# Lavadora.net
KiCad netlist of a schematic drawn in EAGLE
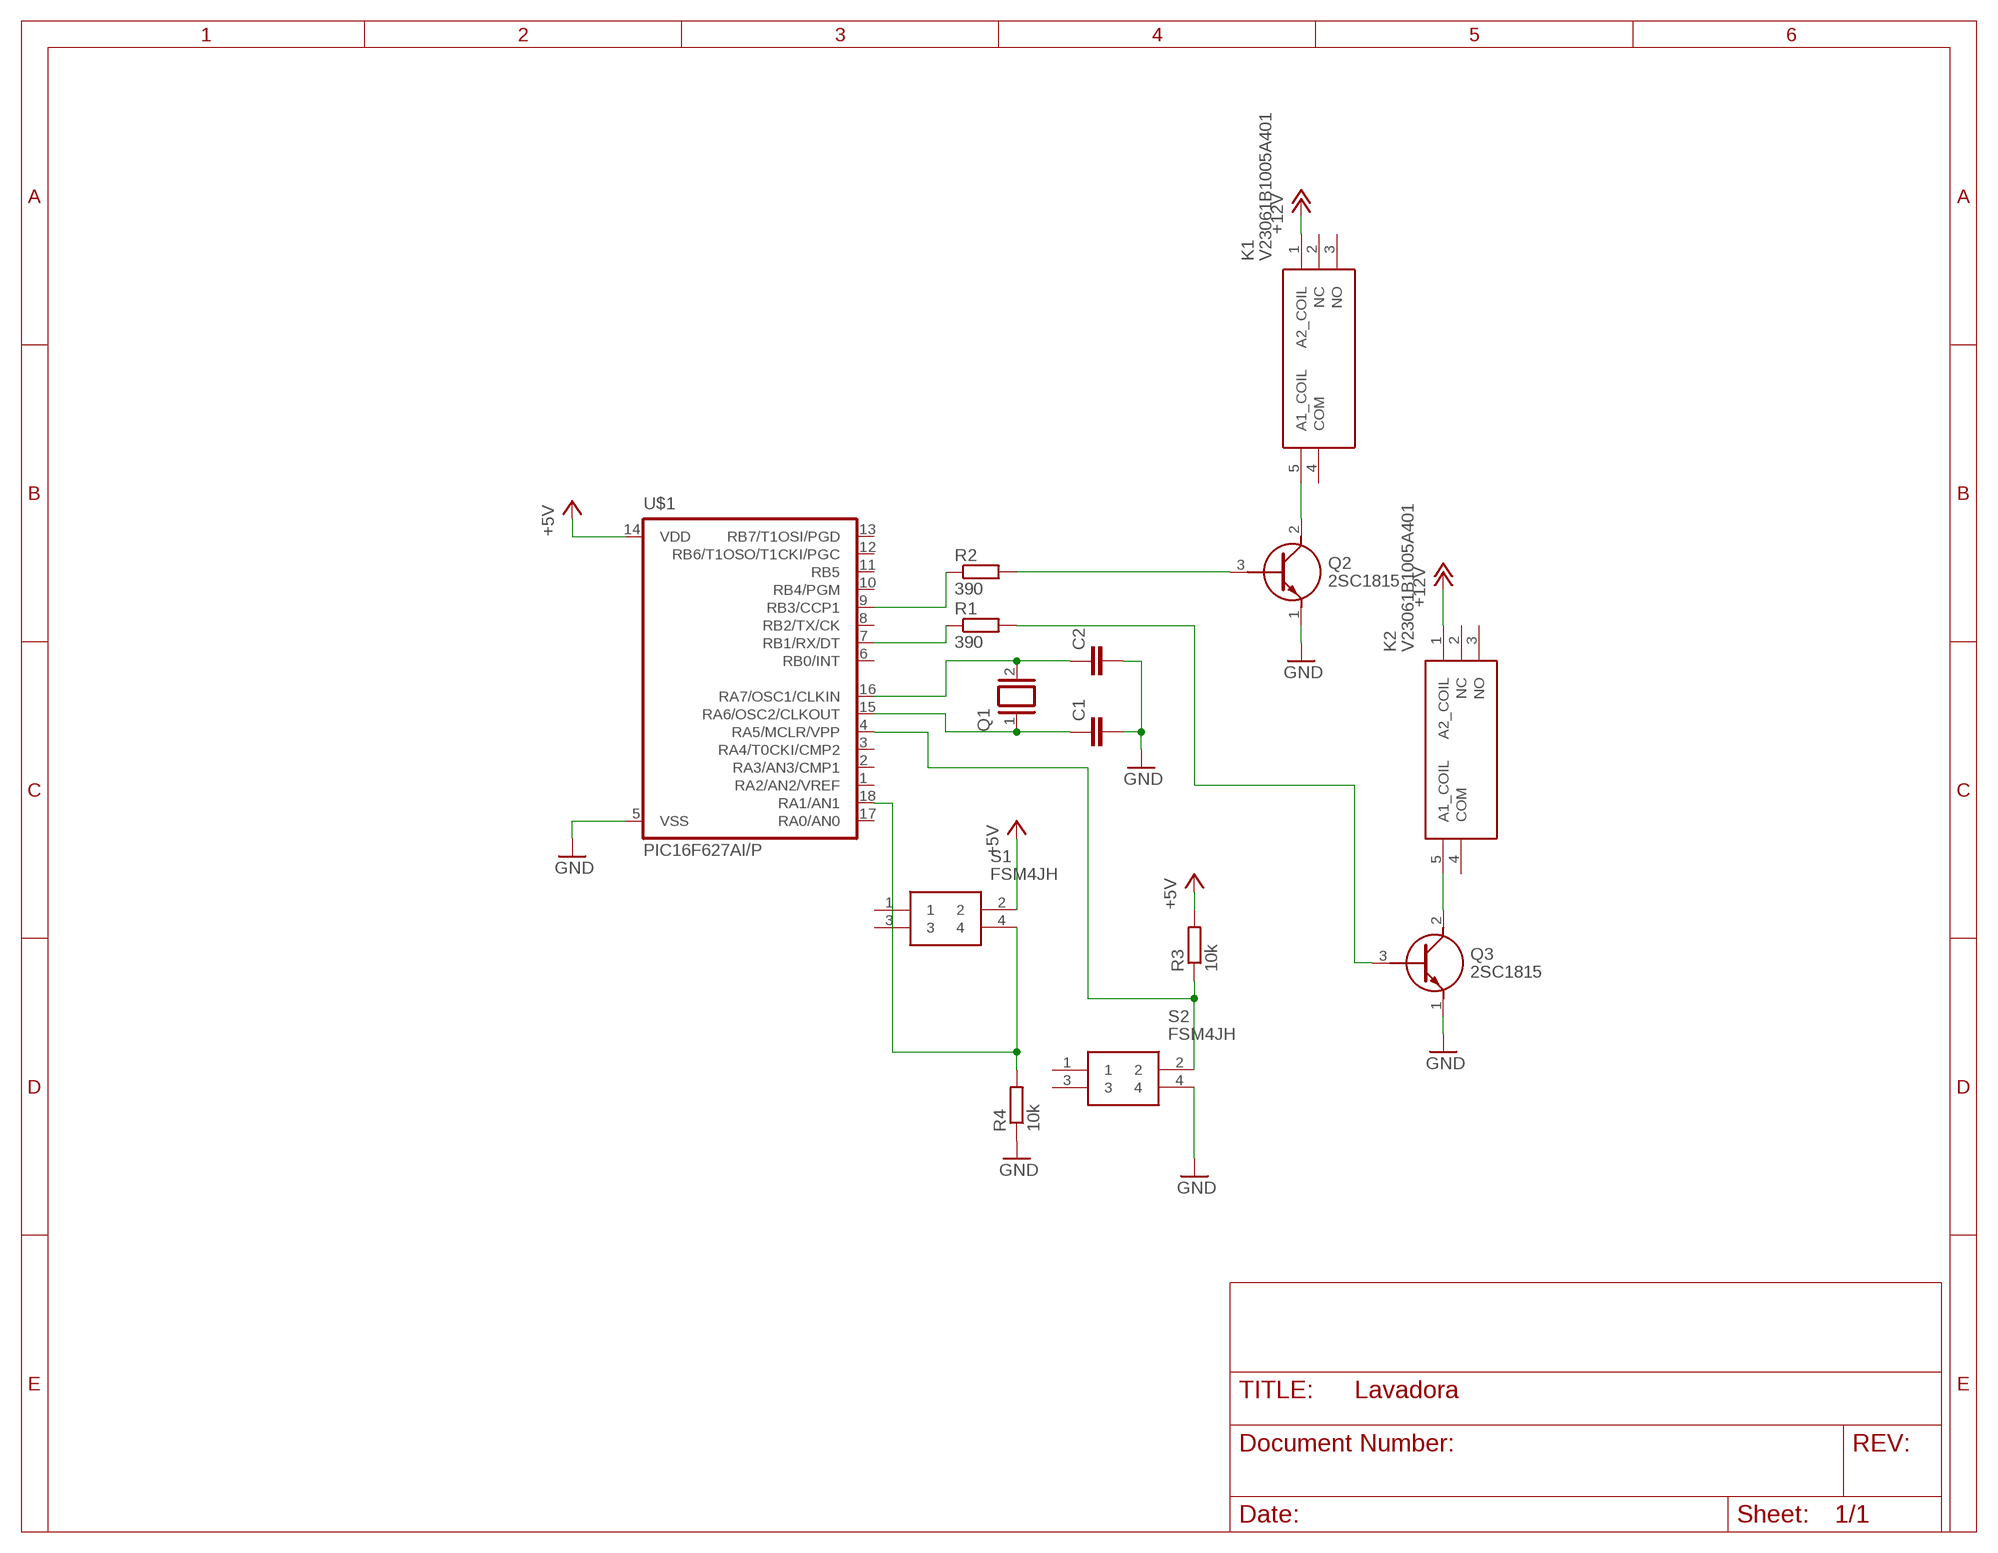
[diagram p0: schematic, sheet 1]

(export (version "E")
  (design (tool "Eeschema 10.0.6"))
  (components
    (comp (ref "C1")
      (value "C-EU025-025X050")
      (footprint "eagle-import:C025-025X050")
      (libsource (lib "eagle-import") (part "C-EU025-025X050"))
    )
    (comp (ref "C2")
      (value "C-EU025-025X050")
      (footprint "eagle-import:C025-025X050")
      (libsource (lib "eagle-import") (part "C-EU025-025X050"))
    )
    (comp (ref "K1")
      (value "V23061B1005A401")
      (footprint "eagle-import:V23061B1005A401")
      (fields (field (name "MOUSER_PART_NUMBER") "655-V23061B1005A401"))
      (libsource (lib "eagle-import") (part "V23061B1005A401"))
    )
    (comp (ref "K2")
      (value "V23061B1005A401")
      (footprint "eagle-import:V23061B1005A401")
      (fields (field (name "MOUSER_PART_NUMBER") "655-V23061B1005A401"))
      (libsource (lib "eagle-import") (part "V23061B1005A401"))
    )
    (comp (ref "Q1")
      (value "XTAL")
      (footprint "eagle-import:Q")
      (libsource (lib "eagle-import") (part "XTAL"))
    )
    (comp (ref "Q2")
      (value "2SC1815")
      (footprint "eagle-import:CS_TO-92")
      (fields (field (name "MOUSER_PART_NUMBER") "610-2SC1815"))
      (libsource (lib "eagle-import") (part "2SC1815"))
    )
    (comp (ref "Q3")
      (value "2SC1815")
      (footprint "eagle-import:CS_TO-92")
      (fields (field (name "MOUSER_PART_NUMBER") "610-2SC1815"))
      (libsource (lib "eagle-import") (part "2SC1815"))
    )
    (comp (ref "R1")
      (value "390")
      (footprint "eagle-import:0207_10")
      (libsource (lib "eagle-import") (part "R-EU_0207/10"))
    )
    (comp (ref "R2")
      (value "390")
      (footprint "eagle-import:0207_10")
      (libsource (lib "eagle-import") (part "R-EU_0207/10"))
    )
    (comp (ref "R3")
      (value "10k")
      (footprint "eagle-import:0207_10")
      (libsource (lib "eagle-import") (part "R-EU_0207/10"))
    )
    (comp (ref "R4")
      (value "10k")
      (footprint "eagle-import:0207_10")
      (libsource (lib "eagle-import") (part "R-EU_0207/10"))
    )
    (comp (ref "S1")
      (value "FSM4JH")
      (footprint "eagle-import:FSM4JH")
      (fields (field (name "MOUSER_PART_NUMBER") "506-FSM4JH"))
      (libsource (lib "eagle-import") (part "FSM4JH"))
    )
    (comp (ref "S2")
      (value "FSM4JH")
      (footprint "eagle-import:FSM4JH")
      (fields (field (name "MOUSER_PART_NUMBER") "506-FSM4JH"))
      (libsource (lib "eagle-import") (part "FSM4JH"))
    )
    (comp (ref "U$1")
      (value "PIC16F627AI/P")
      (footprint "eagle-import:DIL18")
      (libsource (lib "eagle-import") (part "PIC16F627AI/P"))
    )
  )
  (nets
    (net (code "1") (name "+5V") (class "Default")
      (node (ref "R3") (pin "2") (pinfunction "2_2") (pintype "passive"))
      (node (ref "S1") (pin "2") (pinfunction "2_2") (pintype "bidirectional"))
      (node (ref "U$1") (pin "14") (pinfunction "VDD_14") (pintype "power_in"))
    )
    (net (code "2") (name "+12V") (class "Default")
      (node (ref "K1") (pin "1") (pinfunction "A2_COIL_1") (pintype "bidirectional"))
      (node (ref "K2") (pin "1") (pinfunction "A2_COIL_1") (pintype "bidirectional"))
    )
    (net (code "3") (name "GND") (class "Default")
      (node (ref "C1") (pin "2") (pinfunction "2_2") (pintype "passive"))
      (node (ref "C2") (pin "2") (pinfunction "2_2") (pintype "passive"))
      (node (ref "Q2") (pin "1") (pinfunction "E_1") (pintype "bidirectional"))
      (node (ref "Q3") (pin "1") (pinfunction "E_1") (pintype "bidirectional"))
      (node (ref "R4") (pin "1") (pinfunction "1_1") (pintype "passive"))
      (node (ref "S2") (pin "4") (pinfunction "4_4") (pintype "bidirectional"))
      (node (ref "U$1") (pin "5") (pinfunction "VSS_5") (pintype "power_in"))
    )
    (net (code "4") (name "Net-(K1-A1_COIL)") (class "Default")
      (node (ref "K1") (pin "5") (pinfunction "A1_COIL_5") (pintype "bidirectional"))
      (node (ref "Q2") (pin "2") (pinfunction "C_2") (pintype "bidirectional"))
    )
    (net (code "5") (name "Net-(K2-A1_COIL)") (class "Default")
      (node (ref "K2") (pin "5") (pinfunction "A1_COIL_5") (pintype "bidirectional"))
      (node (ref "Q3") (pin "2") (pinfunction "C_2") (pintype "bidirectional"))
    )
    (net (code "6") (name "Net-(Q2-B)") (class "Default")
      (node (ref "Q2") (pin "3") (pinfunction "B_3") (pintype "bidirectional"))
      (node (ref "R2") (pin "2") (pinfunction "2_2") (pintype "passive"))
    )
    (net (code "7") (name "Net-(Q3-B)") (class "Default")
      (node (ref "Q3") (pin "3") (pinfunction "B_3") (pintype "bidirectional"))
      (node (ref "R1") (pin "2") (pinfunction "2_2") (pintype "passive"))
    )
    (net (code "8") (name "Net-(U$1-RA1{slash}AN1)") (class "Default")
      (node (ref "R4") (pin "2") (pinfunction "2_2") (pintype "passive"))
      (node (ref "S1") (pin "4") (pinfunction "4_4") (pintype "bidirectional"))
      (node (ref "U$1") (pin "18") (pinfunction "RA1/AN1_18") (pintype "bidirectional"))
    )
    (net (code "9") (name "Net-(U$1-RA5{slash}MCLR{slash}VPP)") (class "Default")
      (node (ref "R3") (pin "1") (pinfunction "1_1") (pintype "passive"))
      (node (ref "S2") (pin "2") (pinfunction "2_2") (pintype "bidirectional"))
      (node (ref "U$1") (pin "4") (pinfunction "RA5/MCLR/VPP_4") (pintype "bidirectional"))
    )
    (net (code "10") (name "Net-(U$1-RA6{slash}OSC2{slash}CLKOUT)") (class "Default")
      (node (ref "C1") (pin "1") (pinfunction "1_1") (pintype "passive"))
      (node (ref "Q1") (pin "1") (pinfunction "1_1") (pintype "passive"))
      (node (ref "U$1") (pin "15") (pinfunction "RA6/OSC2/CLKOUT_15") (pintype "bidirectional"))
    )
    (net (code "11") (name "Net-(U$1-RA7{slash}OSC1{slash}CLKIN)") (class "Default")
      (node (ref "C2") (pin "1") (pinfunction "1_1") (pintype "passive"))
      (node (ref "Q1") (pin "2") (pinfunction "2_2") (pintype "passive"))
      (node (ref "U$1") (pin "16") (pinfunction "RA7/OSC1/CLKIN_16") (pintype "bidirectional"))
    )
    (net (code "12") (name "Net-(U$1-RB1{slash}RX{slash}DT)") (class "Default")
      (node (ref "R1") (pin "1") (pinfunction "1_1") (pintype "passive"))
      (node (ref "U$1") (pin "7") (pinfunction "RB1/RX/DT_7") (pintype "bidirectional"))
    )
    (net (code "13") (name "Net-(U$1-RB3{slash}CCP1)") (class "Default")
      (node (ref "R2") (pin "1") (pinfunction "1_1") (pintype "passive"))
      (node (ref "U$1") (pin "9") (pinfunction "RB3/CCP1_9") (pintype "bidirectional"))
    )
    (net (code "14") (name "unconnected-(K1-COM-Pad4)") (class "Default")
      (node (ref "K1") (pin "4") (pinfunction "COM_4") (pintype "bidirectional"))
    )
    (net (code "15") (name "unconnected-(K1-NC-Pad2)") (class "Default")
      (node (ref "K1") (pin "2") (pinfunction "NC_2") (pintype "no_connect"))
    )
    (net (code "16") (name "unconnected-(K1-NO-Pad3)") (class "Default")
      (node (ref "K1") (pin "3") (pinfunction "NO_3") (pintype "bidirectional"))
    )
    (net (code "17") (name "unconnected-(K2-COM-Pad4)") (class "Default")
      (node (ref "K2") (pin "4") (pinfunction "COM_4") (pintype "bidirectional"))
    )
    (net (code "18") (name "unconnected-(K2-NC-Pad2)") (class "Default")
      (node (ref "K2") (pin "2") (pinfunction "NC_2") (pintype "no_connect"))
    )
    (net (code "19") (name "unconnected-(K2-NO-Pad3)") (class "Default")
      (node (ref "K2") (pin "3") (pinfunction "NO_3") (pintype "bidirectional"))
    )
    (net (code "20") (name "unconnected-(S1-Pad1)") (class "Default")
      (node (ref "S1") (pin "1") (pinfunction "1_1") (pintype "bidirectional"))
    )
    (net (code "21") (name "unconnected-(S1-Pad3)") (class "Default")
      (node (ref "S1") (pin "3") (pinfunction "3_3") (pintype "bidirectional"))
    )
    (net (code "22") (name "unconnected-(S2-Pad1)") (class "Default")
      (node (ref "S2") (pin "1") (pinfunction "1_1") (pintype "bidirectional"))
    )
    (net (code "23") (name "unconnected-(S2-Pad3)") (class "Default")
      (node (ref "S2") (pin "3") (pinfunction "3_3") (pintype "bidirectional"))
    )
    (net (code "24") (name "unconnected-(U$1-RA0{slash}AN0-Pad17)") (class "Default")
      (node (ref "U$1") (pin "17") (pinfunction "RA0/AN0_17") (pintype "bidirectional"))
    )
    (net (code "25") (name "unconnected-(U$1-RA2{slash}AN2{slash}VREF-Pad1)") (class "Default")
      (node (ref "U$1") (pin "1") (pinfunction "RA2/AN2/VREF_1") (pintype "bidirectional"))
    )
    (net (code "26") (name "unconnected-(U$1-RA3{slash}AN3{slash}CMP1-Pad2)") (class "Default")
      (node (ref "U$1") (pin "2") (pinfunction "RA3/AN3/CMP1_2") (pintype "bidirectional"))
    )
    (net (code "27") (name "unconnected-(U$1-RA4{slash}T0CKI{slash}CMP2-Pad3)") (class "Default")
      (node (ref "U$1") (pin "3") (pinfunction "RA4/T0CKI/CMP2_3") (pintype "bidirectional"))
    )
    (net (code "28") (name "unconnected-(U$1-RB0{slash}INT-Pad6)") (class "Default")
      (node (ref "U$1") (pin "6") (pinfunction "RB0/INT_6") (pintype "bidirectional"))
    )
    (net (code "29") (name "unconnected-(U$1-RB2{slash}TX{slash}CK-Pad8)") (class "Default")
      (node (ref "U$1") (pin "8") (pinfunction "RB2/TX/CK_8") (pintype "bidirectional"))
    )
    (net (code "30") (name "unconnected-(U$1-RB4{slash}PGM-Pad10)") (class "Default")
      (node (ref "U$1") (pin "10") (pinfunction "RB4/PGM_10") (pintype "bidirectional"))
    )
    (net (code "31") (name "unconnected-(U$1-RB5-Pad11)") (class "Default")
      (node (ref "U$1") (pin "11") (pinfunction "RB5_11") (pintype "bidirectional"))
    )
    (net (code "32") (name "unconnected-(U$1-RB6{slash}T1OSO{slash}T1CKI{slash}PGC-Pad12)") (class "Default")
      (node (ref "U$1") (pin "12") (pinfunction "RB6/T1OSO/T1CKI/PGC_12") (pintype "bidirectional"))
    )
    (net (code "33") (name "unconnected-(U$1-RB7{slash}T1OSI{slash}PGD-Pad13)") (class "Default")
      (node (ref "U$1") (pin "13") (pinfunction "RB7/T1OSI/PGD_13") (pintype "bidirectional"))
    )
  )
)
